# Teensy_Polulu_8848.net
KiCad netlist of a schematic drawn in EAGLE
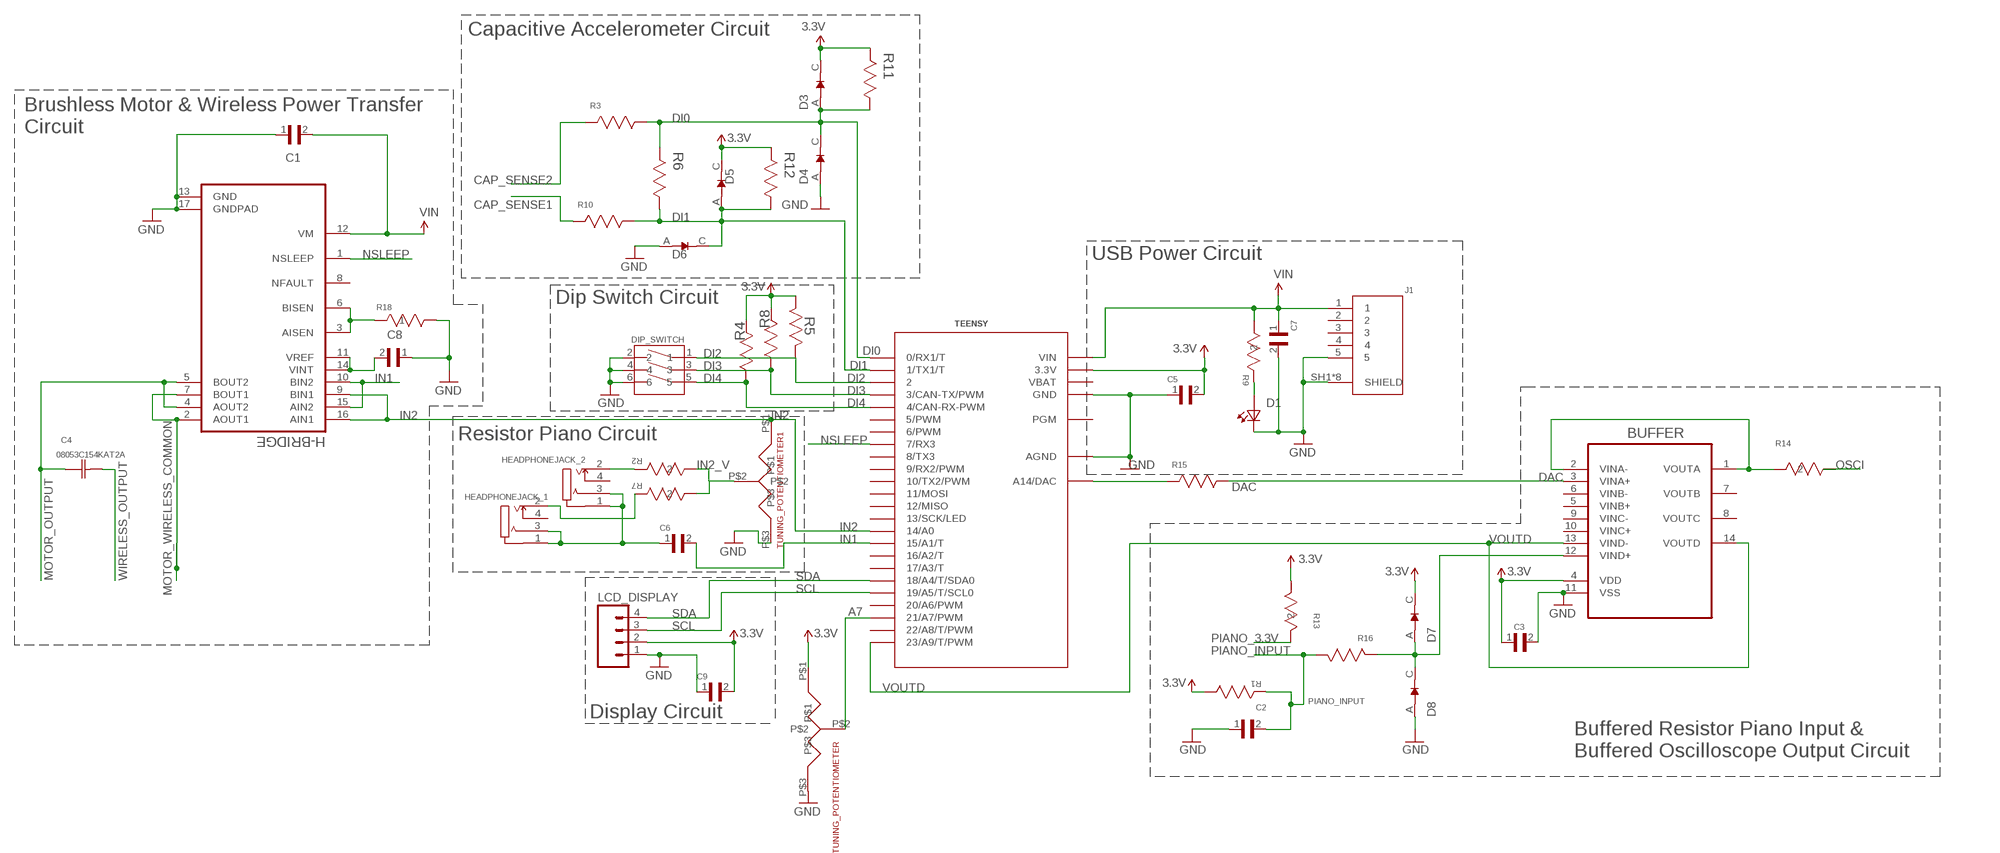
[diagram p0: schematic, sheet 1]

(export (version "E")
  (design (tool "Eeschema 10.0.6"))
  (components
    (comp (ref "BUFFER")
      (value "MCP6024-I/SL")
      (footprint "eagle-import:SOIC127P600X175-14N")
      (fields (field (name "DIGI-KEY_PART_NUMBER") "MCP6024-I/SL-ND") (field (name "MF") "Microchip"))
      (libsource (lib "eagle-import") (part "MCP6024-I/SL"))
    )
    (comp (ref "C1")
      (value "GRM219R60J476ME44D")
      (footprint "eagle-import:CAPC2012X135N")
      (fields (field (name "DIGI-KEY_PART_NUMBER") "490-13249-1-ND") (field (name "MF") "Murata"))
      (libsource (lib "eagle-import") (part "GRM219R60J476ME44D"))
    )
    (comp (ref "C2")
      (value "C2012C0G1V303J060AC")
      (footprint "eagle-import:INDC2012X87N")
      (fields (field (name "MF") "TDK"))
      (libsource (lib "eagle-import") (part "C2012C0G1V303J060AC"))
    )
    (comp (ref "C3")
      (value "GRM219R60J476ME44D")
      (footprint "eagle-import:CAPC2012X135N")
      (fields (field (name "DIGI-KEY_PART_NUMBER") "490-13249-1-ND") (field (name "MF") "Murata"))
      (libsource (lib "eagle-import") (part "GRM219R60J476ME44D"))
    )
    (comp (ref "C4")
      (value "08053C154KAT2A")
      (footprint "eagle-import:CAPC2013X94N")
      (fields (field (name "MF") "AVX"))
      (libsource (lib "eagle-import") (part "08053C154KAT2A"))
    )
    (comp (ref "C5")
      (value "GRM219R60J476ME44D")
      (footprint "eagle-import:CAPC2012X135N")
      (fields (field (name "DIGI-KEY_PART_NUMBER") "490-13249-1-ND") (field (name "MF") "Murata"))
      (libsource (lib "eagle-import") (part "GRM219R60J476ME44D"))
    )
    (comp (ref "C6")
      (value "GRM219R60J476ME44D")
      (footprint "eagle-import:CAPC2012X135N")
      (fields (field (name "DIGI-KEY_PART_NUMBER") "490-13249-1-ND") (field (name "MF") "Murata"))
      (libsource (lib "eagle-import") (part "GRM219R60J476ME44D"))
    )
    (comp (ref "C7")
      (value "GRM219R60J476ME44D")
      (footprint "eagle-import:CAPC2012X135N")
      (fields (field (name "DIGI-KEY_PART_NUMBER") "490-13249-1-ND") (field (name "MF") "Murata"))
      (libsource (lib "eagle-import") (part "GRM219R60J476ME44D"))
    )
    (comp (ref "C8")
      (value "GRM21BR60J225KA01L")
      (footprint "eagle-import:CAPC2012X135N")
      (fields (field (name "DIGI-KEY_PART_NUMBER") "490-1712-1-ND") (field (name "MF") "Murata"))
      (libsource (lib "eagle-import") (part "GRM21BR60J225KA01L"))
    )
    (comp (ref "C9")
      (value "GRM219R60J476ME44D")
      (footprint "eagle-import:CAPC2012X135N")
      (fields (field (name "DIGI-KEY_PART_NUMBER") "490-13249-1-ND") (field (name "MF") "Murata"))
      (libsource (lib "eagle-import") (part "GRM219R60J476ME44D"))
    )
    (comp (ref "D1")
      (value "TLMY1100-GS08")
      (footprint "eagle-import:0603")
      (fields (field (name "MF") "Vishay Semiconductor"))
      (libsource (lib "eagle-import") (part "TLMY1100-GS08"))
    )
    (comp (ref "D3")
      (value "1N4148W-7-F")
      (footprint "eagle-import:SOD3715X135N")
      (fields (field (name "MF") "Diodes Inc."))
      (libsource (lib "eagle-import") (part "1N4148W-7-F"))
    )
    (comp (ref "D4")
      (value "1N4148W-7-F")
      (footprint "eagle-import:SOD3715X135N")
      (fields (field (name "MF") "Diodes Inc."))
      (libsource (lib "eagle-import") (part "1N4148W-7-F"))
    )
    (comp (ref "D5")
      (value "1N4148W-7-F")
      (footprint "eagle-import:SOD3715X135N")
      (fields (field (name "MF") "Diodes Inc."))
      (libsource (lib "eagle-import") (part "1N4148W-7-F"))
    )
    (comp (ref "D6")
      (value "1N4148W-7-F")
      (footprint "eagle-import:SOD3715X135N")
      (fields (field (name "MF") "Diodes Inc."))
      (libsource (lib "eagle-import") (part "1N4148W-7-F"))
    )
    (comp (ref "D7")
      (value "1N4148W-7-F")
      (footprint "eagle-import:SOD3715X135N")
      (fields (field (name "MF") "Diodes Inc."))
      (libsource (lib "eagle-import") (part "1N4148W-7-F"))
    )
    (comp (ref "D8")
      (value "1N4148W-7-F")
      (footprint "eagle-import:SOD3715X135N")
      (fields (field (name "MF") "Diodes Inc."))
      (libsource (lib "eagle-import") (part "1N4148W-7-F"))
    )
    (comp (ref "DIP_SWITCH")
      (value "SDA03H1SBD")
      (footprint "eagle-import:SW_SDA03H1SBD")
      (fields (field (name "MF") "C&K"))
      (libsource (lib "eagle-import") (part "SDA03H1SBD"))
    )
    (comp (ref "H-BRIDGE")
      (value "DRV8848PWP")
      (footprint "eagle-import:SOP65P640X120-17N")
      (fields (field (name "MF") "Texas Instruments"))
      (libsource (lib "eagle-import") (part "DRV8848PWP"))
    )
    (comp (ref "HEADPHONEJACK_1")
      (value "47257-0001")
      (footprint "eagle-import:MOLEX_47257-0001")
      (fields (field (name "MF") "Molex"))
      (libsource (lib "eagle-import") (part "47257-0001"))
    )
    (comp (ref "HEADPHONEJACK_2")
      (value "47257-0001")
      (footprint "eagle-import:MOLEX_47257-0001")
      (fields (field (name "MF") "Molex"))
      (libsource (lib "eagle-import") (part "47257-0001"))
    )
    (comp (ref "J1")
      (value "1050170001")
      (footprint "eagle-import:MOLEX_1050170001")
      (fields (field (name "DIGI-KEY_PART_NUMBER") "WM1399CT-ND") (field (name "MF") "Molex"))
      (libsource (lib "eagle-import") (part "1050170001"))
    )
    (comp (ref "LCD_DISPLAY")
      (value "M04POLAR")
      (footprint "eagle-import:MOLEX-1X4")
      (libsource (lib "eagle-import") (part "M04POLAR"))
    )
    (comp (ref "R1")
      (value "RT0805FRE071ML")
      (footprint "eagle-import:RESC2013X65N")
      (fields (field (name "MF") "Yageo"))
      (libsource (lib "eagle-import") (part "RT0805FRE071ML"))
    )
    (comp (ref "R2")
      (value "RT0805FRE07100RL")
      (footprint "eagle-import:RC0805N")
      (libsource (lib "eagle-import") (part "RT0805FRE07100RL"))
    )
    (comp (ref "R3")
      (value "RT0805FRE0710KL")
      (footprint "eagle-import:RESC2013X65N")
      (fields (field (name "MF") "Yageo") (field (name "SPICEPREFIX") "R"))
      (libsource (lib "eagle-import") (part "RT0805FRE0710KL"))
    )
    (comp (ref "R4")
      (value "RT0805FRE0710KL")
      (footprint "eagle-import:RESC2013X65N")
      (fields (field (name "MF") "Yageo"))
      (libsource (lib "eagle-import") (part "RT0805FRE0710KL"))
    )
    (comp (ref "R5")
      (value "RT0805FRE0710KL")
      (footprint "eagle-import:RESC2013X65N")
      (fields (field (name "MF") "Yageo"))
      (libsource (lib "eagle-import") (part "RT0805FRE0710KL"))
    )
    (comp (ref "R6")
      (value "RT0805FRE071ML")
      (footprint "eagle-import:RESC2013X65N")
      (fields (field (name "MF") "Yageo"))
      (libsource (lib "eagle-import") (part "RT0805FRE071ML"))
    )
    (comp (ref "R7")
      (value "RT0805FRE07100RL")
      (footprint "eagle-import:RC0805N")
      (libsource (lib "eagle-import") (part "RT0805FRE07100RL"))
    )
    (comp (ref "R8")
      (value "RT0805FRE0710KL")
      (footprint "eagle-import:RESC2013X65N")
      (fields (field (name "MF") "Yageo"))
      (libsource (lib "eagle-import") (part "RT0805FRE0710KL"))
    )
    (comp (ref "R9")
      (value "RT0805FRE071KL")
      (footprint "eagle-import:RC0805N")
      (libsource (lib "eagle-import") (part "RT0805FRE071KL"))
    )
    (comp (ref "R10")
      (value "RT0805FRE0710KL")
      (footprint "eagle-import:RESC2013X65N")
      (fields (field (name "MF") "Yageo") (field (name "SPICEPREFIX") "R"))
      (libsource (lib "eagle-import") (part "RT0805FRE0710KL"))
    )
    (comp (ref "R11")
      (value "RT0805FRE071ML")
      (footprint "eagle-import:RESC2013X65N")
      (fields (field (name "MF") "Yageo"))
      (libsource (lib "eagle-import") (part "RT0805FRE071ML"))
    )
    (comp (ref "R12")
      (value "RT0805FRE071ML")
      (footprint "eagle-import:RESC2013X65N")
      (fields (field (name "MF") "Yageo"))
      (libsource (lib "eagle-import") (part "RT0805FRE071ML"))
    )
    (comp (ref "R13")
      (value "RT0805BRD0749R9L")
      (footprint "eagle-import:RC0805N")
      (libsource (lib "eagle-import") (part "RT0805BRD0749R9L"))
    )
    (comp (ref "R14")
      (value "RT0805FRE071KL")
      (footprint "eagle-import:RC0805N")
      (libsource (lib "eagle-import") (part "RT0805FRE071KL"))
    )
    (comp (ref "R15")
      (value "RT0805FRE0710KL")
      (footprint "eagle-import:RESC2013X65N")
      (fields (field (name "MF") "Yageo") (field (name "SPICEPREFIX") "R"))
      (libsource (lib "eagle-import") (part "RT0805FRE0710KL"))
    )
    (comp (ref "R16")
      (value "RT0805FRE0710KL")
      (footprint "eagle-import:RESC2013X65N")
      (fields (field (name "MF") "Yageo") (field (name "SPICEPREFIX") "R"))
      (libsource (lib "eagle-import") (part "RT0805FRE0710KL"))
    )
    (comp (ref "R18")
      (value "CSRN2512FKR250")
      (footprint "eagle-import:STA_CSRN2512")
      (libsource (lib "eagle-import") (part "CSRN2512FKR250"))
    )
    (comp (ref "TEENSY")
      (value "TEENSY_3.1-3.2_OUTER_ROW")
      (footprint "eagle-import:TEENSY_3.0-3.2&LC_OUTER_ROW")
      (libsource (lib "eagle-import") (part "TEENSY_3.1-3.2_OUTER_ROW"))
    )
    (comp (ref "TUNING_POTENTIOMETER")
      (value "POT_PTV09A-4225F-B102-ND")
      (footprint "eagle-import:POT_PTV09A-4225F-B102-ND")
      (libsource (lib "eagle-import") (part "POT_PTV09A-4225F-B102-ND"))
    )
    (comp (ref "TUNING_POTENTIOMETER1")
      (value "POT_PTV09A-4225F-B102-ND")
      (footprint "eagle-import:POT_PTV09A-4225F-B102-ND")
      (libsource (lib "eagle-import") (part "POT_PTV09A-4225F-B102-ND"))
    )
  )
  (nets
    (net (code "1") (name "/A7") (class "Default")
      (node (ref "TEENSY") (pin "21/A7") (pinfunction "21/A7/PWM_21/A7") (pintype "bidirectional"))
      (node (ref "TUNING_POTENTIOMETER") (pin "P$2") (pinfunction "P$2_P$2") (pintype "bidirectional"))
    )
    (net (code "2") (name "/CAP_SENSE1") (class "Default")
      (node (ref "R10") (pin "2") (pinfunction "R2_2") (pintype "passive"))
    )
    (net (code "3") (name "/CAP_SENSE2") (class "Default")
      (node (ref "R3") (pin "2") (pinfunction "R2_2") (pintype "passive"))
    )
    (net (code "4") (name "/DAC") (class "Default")
      (node (ref "BUFFER") (pin "3") (pinfunction "VINA+_3") (pintype "input"))
      (node (ref "R15") (pin "1") (pinfunction "R1_1") (pintype "passive"))
    )
    (net (code "5") (name "/DI0") (class "Default")
      (node (ref "D3") (pin "A") (pinfunction "A_A") (pintype "passive"))
      (node (ref "D4") (pin "C") (pinfunction "K_C") (pintype "passive"))
      (node (ref "R11") (pin "1") (pinfunction "R1_1") (pintype "passive"))
      (node (ref "R3") (pin "1") (pinfunction "R1_1") (pintype "passive"))
      (node (ref "R6") (pin "2") (pinfunction "R2_2") (pintype "passive"))
      (node (ref "TEENSY") (pin "0") (pinfunction "0/RX1/T_0") (pintype "bidirectional"))
    )
    (net (code "6") (name "/DI1") (class "Default")
      (node (ref "D5") (pin "A") (pinfunction "A_A") (pintype "passive"))
      (node (ref "D6") (pin "C") (pinfunction "K_C") (pintype "passive"))
      (node (ref "R10") (pin "1") (pinfunction "R1_1") (pintype "passive"))
      (node (ref "R12") (pin "1") (pinfunction "R1_1") (pintype "passive"))
      (node (ref "R6") (pin "1") (pinfunction "R1_1") (pintype "passive"))
      (node (ref "TEENSY") (pin "1") (pinfunction "1/TX1/T_1") (pintype "bidirectional"))
    )
    (net (code "7") (name "/DI2") (class "Default")
      (node (ref "DIP_SWITCH") (pin "1") (pinfunction "1_1") (pintype "passive"))
      (node (ref "R5") (pin "2") (pinfunction "R2_2") (pintype "passive"))
      (node (ref "TEENSY") (pin "2") (pinfunction "2_2") (pintype "bidirectional"))
    )
    (net (code "8") (name "/DI3") (class "Default")
      (node (ref "DIP_SWITCH") (pin "3") (pinfunction "3_3") (pintype "passive"))
      (node (ref "R8") (pin "2") (pinfunction "R2_2") (pintype "passive"))
      (node (ref "TEENSY") (pin "3") (pinfunction "3/CAN-TX/PWM_3") (pintype "bidirectional"))
    )
    (net (code "9") (name "/DI4") (class "Default")
      (node (ref "DIP_SWITCH") (pin "5") (pinfunction "5_5") (pintype "passive"))
      (node (ref "R4") (pin "2") (pinfunction "R2_2") (pintype "passive"))
      (node (ref "TEENSY") (pin "4") (pinfunction "4/CAN-RX-PWM_4") (pintype "bidirectional"))
    )
    (net (code "10") (name "/IN1") (class "Default")
      (node (ref "C6") (pin "2") (pinfunction "2_2") (pintype "passive"))
      (node (ref "H-BRIDGE") (pin "10") (pinfunction "BIN2_10") (pintype "input"))
      (node (ref "H-BRIDGE") (pin "15") (pinfunction "AIN2_15") (pintype "input"))
      (node (ref "TEENSY") (pin "15/A1") (pinfunction "15/A1/T_15/A1") (pintype "bidirectional"))
    )
    (net (code "11") (name "/IN2") (class "Default")
      (node (ref "H-BRIDGE") (pin "16") (pinfunction "AIN1_16") (pintype "input"))
      (node (ref "H-BRIDGE") (pin "9") (pinfunction "BIN1_9") (pintype "input"))
      (node (ref "TEENSY") (pin "14/A0") (pinfunction "14/A0_14/A0") (pintype "bidirectional"))
      (node (ref "TUNING_POTENTIOMETER1") (pin "P$1") (pinfunction "P$1_P$1") (pintype "bidirectional"))
    )
    (net (code "12") (name "/IN2_V") (class "Default")
      (node (ref "R2") (pin "2") (pinfunction "2_2") (pintype "passive"))
      (node (ref "R7") (pin "2") (pinfunction "2_2") (pintype "passive"))
      (node (ref "TUNING_POTENTIOMETER1") (pin "P$2") (pinfunction "P$2_P$2") (pintype "bidirectional"))
    )
    (net (code "13") (name "/MOTOR_OUTPUT") (class "Default")
      (node (ref "C4") (pin "1") (pinfunction "C1_1") (pintype "passive"))
      (node (ref "H-BRIDGE") (pin "4") (pinfunction "AOUT2_4") (pintype "output"))
      (node (ref "H-BRIDGE") (pin "5") (pinfunction "BOUT2_5") (pintype "output"))
    )
    (net (code "14") (name "/MOTOR_WIRELESS_COMMON") (class "Default")
      (node (ref "H-BRIDGE") (pin "2") (pinfunction "AOUT1_2") (pintype "output"))
      (node (ref "H-BRIDGE") (pin "7") (pinfunction "BOUT1_7") (pintype "output"))
    )
    (net (code "15") (name "/NSLEEP") (class "Default")
      (node (ref "H-BRIDGE") (pin "1") (pinfunction "NSLEEP_1") (pintype "bidirectional"))
      (node (ref "TEENSY") (pin "7") (pinfunction "7/RX3_7") (pintype "bidirectional"))
    )
    (net (code "16") (name "/OSCI") (class "Default")
      (node (ref "R14") (pin "1") (pinfunction "1_1") (pintype "passive"))
    )
    (net (code "17") (name "/PIANO_3.3V") (class "Default")
      (node (ref "R13") (pin "2") (pinfunction "2_2") (pintype "passive"))
    )
    (net (code "18") (name "/PIANO_INPUT") (class "Default")
      (node (ref "C2") (pin "2") (pinfunction "2_2") (pintype "passive"))
      (node (ref "R1") (pin "2") (pinfunction "R2_2") (pintype "passive"))
      (node (ref "R16") (pin "1") (pinfunction "R1_1") (pintype "passive"))
    )
    (net (code "19") (name "/SCL") (class "Default")
      (node (ref "LCD_DISPLAY") (pin "3") (pinfunction "3_3") (pintype "passive"))
      (node (ref "TEENSY") (pin "19/A5") (pinfunction "19/A5/T/SCL0_19/A5") (pintype "bidirectional"))
    )
    (net (code "20") (name "/SDA") (class "Default")
      (node (ref "LCD_DISPLAY") (pin "4") (pinfunction "4_4") (pintype "passive"))
      (node (ref "TEENSY") (pin "18/A4") (pinfunction "18/A4/T/SDA0_18/A4") (pintype "bidirectional"))
    )
    (net (code "21") (name "/VBAT") (class "Default")
      (node (ref "TEENSY") (pin "VBAT") (pinfunction "VBAT_VBAT") (pintype "power_in"))
    )
    (net (code "22") (name "/VOUTD") (class "Default")
      (node (ref "BUFFER") (pin "13") (pinfunction "VIND-_13") (pintype "input"))
      (node (ref "BUFFER") (pin "14") (pinfunction "VOUTD_14") (pintype "output"))
      (node (ref "TEENSY") (pin "23/A9") (pinfunction "23/A9/T/PWM_23/A9") (pintype "bidirectional"))
    )
    (net (code "23") (name "/WIRELESS_OUTPUT") (class "Default")
      (node (ref "C4") (pin "2") (pinfunction "C2_2") (pintype "passive"))
    )
    (net (code "24") (name "3.3V") (class "Default")
      (node (ref "BUFFER") (pin "4") (pinfunction "VDD_4") (pintype "power_in"))
      (node (ref "C3") (pin "1") (pinfunction "1_1") (pintype "passive"))
      (node (ref "C5") (pin "2") (pinfunction "2_2") (pintype "passive"))
      (node (ref "C9") (pin "2") (pinfunction "2_2") (pintype "passive"))
      (node (ref "D3") (pin "C") (pinfunction "K_C") (pintype "passive"))
      (node (ref "D5") (pin "C") (pinfunction "K_C") (pintype "passive"))
      (node (ref "D7") (pin "C") (pinfunction "K_C") (pintype "passive"))
      (node (ref "LCD_DISPLAY") (pin "2") (pinfunction "2_2") (pintype "passive"))
      (node (ref "R1") (pin "1") (pinfunction "R1_1") (pintype "passive"))
      (node (ref "R11") (pin "2") (pinfunction "R2_2") (pintype "passive"))
      (node (ref "R12") (pin "2") (pinfunction "R2_2") (pintype "passive"))
      (node (ref "R13") (pin "1") (pinfunction "1_1") (pintype "passive"))
      (node (ref "R4") (pin "1") (pinfunction "R1_1") (pintype "passive"))
      (node (ref "R5") (pin "1") (pinfunction "R1_1") (pintype "passive"))
      (node (ref "R8") (pin "1") (pinfunction "R1_1") (pintype "passive"))
      (node (ref "TEENSY") (pin "3.3V") (pinfunction "3.3V_3.3V") (pintype "power_in"))
      (node (ref "TEENSY") (pin "3.3V1") (pinfunction "3.3V_3.3V1") (pintype "power_in"))
      (node (ref "TUNING_POTENTIOMETER") (pin "P$1") (pinfunction "P$1_P$1") (pintype "bidirectional"))
    )
    (net (code "25") (name "GND") (class "Default")
      (node (ref "BUFFER") (pin "11") (pinfunction "VSS_11") (pintype "passive"))
      (node (ref "C1") (pin "1") (pinfunction "1_1") (pintype "passive"))
      (node (ref "C2") (pin "1") (pinfunction "1_1") (pintype "passive"))
      (node (ref "C3") (pin "2") (pinfunction "2_2") (pintype "passive"))
      (node (ref "C5") (pin "1") (pinfunction "1_1") (pintype "passive"))
      (node (ref "C7") (pin "2") (pinfunction "2_2") (pintype "passive"))
      (node (ref "C8") (pin "1") (pinfunction "1_1") (pintype "passive"))
      (node (ref "C9") (pin "1") (pinfunction "1_1") (pintype "passive"))
      (node (ref "D1") (pin "1") (pinfunction "K2_1") (pintype "passive"))
      (node (ref "D4") (pin "A") (pinfunction "A_A") (pintype "passive"))
      (node (ref "D6") (pin "A") (pinfunction "A_A") (pintype "passive"))
      (node (ref "D8") (pin "A") (pinfunction "A_A") (pintype "passive"))
      (node (ref "DIP_SWITCH") (pin "2") (pinfunction "2_2") (pintype "passive"))
      (node (ref "DIP_SWITCH") (pin "4") (pinfunction "4_4") (pintype "passive"))
      (node (ref "DIP_SWITCH") (pin "6") (pinfunction "6_6") (pintype "passive"))
      (node (ref "H-BRIDGE") (pin "13") (pinfunction "GND_13") (pintype "power_in"))
      (node (ref "H-BRIDGE") (pin "17") (pinfunction "GNDPAD_17") (pintype "power_in"))
      (node (ref "J1") (pin "5") (pinfunction "5_5") (pintype "passive"))
      (node (ref "J1") (pin "SH1") (pinfunction "SHIELD_SH1") (pintype "passive"))
      (node (ref "J1") (pin "SH2") (pinfunction "SHIELD_SH2") (pintype "passive"))
      (node (ref "J1") (pin "SH3") (pinfunction "SHIELD_SH3") (pintype "passive"))
      (node (ref "J1") (pin "SH4") (pinfunction "SHIELD_SH4") (pintype "passive"))
      (node (ref "J1") (pin "SH5") (pinfunction "SHIELD_SH5") (pintype "passive"))
      (node (ref "J1") (pin "SH6") (pinfunction "SHIELD_SH6") (pintype "passive"))
      (node (ref "J1") (pin "SH7") (pinfunction "SHIELD_SH7") (pintype "passive"))
      (node (ref "J1") (pin "SH8") (pinfunction "SHIELD_SH8") (pintype "passive"))
      (node (ref "LCD_DISPLAY") (pin "1") (pinfunction "1_1") (pintype "passive"))
      (node (ref "R18") (pin "2") (pinfunction "2_2") (pintype "passive"))
      (node (ref "TEENSY") (pin "AGND") (pinfunction "AGND_AGND") (pintype "power_in"))
      (node (ref "TEENSY") (pin "GND") (pinfunction "GND_GND") (pintype "power_in"))
      (node (ref "TEENSY") (pin "GND1") (pinfunction "GND_GND1") (pintype "power_in"))
      (node (ref "TUNING_POTENTIOMETER") (pin "P$3") (pinfunction "P$3_P$3") (pintype "bidirectional"))
      (node (ref "TUNING_POTENTIOMETER1") (pin "P$3") (pinfunction "P$3_P$3") (pintype "bidirectional"))
    )
    (net (code "26") (name "Net-(BUFFER-VINA-)") (class "Default")
      (node (ref "BUFFER") (pin "1") (pinfunction "VOUTA_1") (pintype "output"))
      (node (ref "BUFFER") (pin "2") (pinfunction "VINA-_2") (pintype "input"))
      (node (ref "R14") (pin "2") (pinfunction "2_2") (pintype "passive"))
    )
    (net (code "27") (name "Net-(BUFFER-VIND+)") (class "Default")
      (node (ref "BUFFER") (pin "12") (pinfunction "VIND+_12") (pintype "input"))
      (node (ref "D7") (pin "A") (pinfunction "A_A") (pintype "passive"))
      (node (ref "D8") (pin "C") (pinfunction "K_C") (pintype "passive"))
      (node (ref "R16") (pin "2") (pinfunction "R2_2") (pintype "passive"))
    )
    (net (code "28") (name "Net-(C6-Pad1)") (class "Default")
      (node (ref "C6") (pin "1") (pinfunction "1_1") (pintype "passive"))
      (node (ref "HEADPHONEJACK_1") (pin "1") (pinfunction "1_1") (pintype "passive"))
      (node (ref "HEADPHONEJACK_1") (pin "3") (pinfunction "3_3") (pintype "passive"))
      (node (ref "HEADPHONEJACK_2") (pin "1") (pinfunction "1_1") (pintype "passive"))
      (node (ref "HEADPHONEJACK_2") (pin "3") (pinfunction "3_3") (pintype "passive"))
    )
    (net (code "29") (name "Net-(D1-A2)") (class "Default")
      (node (ref "D1") (pin "2") (pinfunction "A2_2") (pintype "passive"))
      (node (ref "R9") (pin "1") (pinfunction "1_1") (pintype "passive"))
    )
    (net (code "30") (name "Net-(H-BRIDGE-AISEN)") (class "Default")
      (node (ref "H-BRIDGE") (pin "3") (pinfunction "AISEN_3") (pintype "bidirectional"))
      (node (ref "H-BRIDGE") (pin "6") (pinfunction "BISEN_6") (pintype "bidirectional"))
      (node (ref "R18") (pin "1") (pinfunction "1_1") (pintype "passive"))
    )
    (net (code "31") (name "Net-(H-BRIDGE-VINT)") (class "Default")
      (node (ref "C8") (pin "2") (pinfunction "2_2") (pintype "passive"))
      (node (ref "H-BRIDGE") (pin "11") (pinfunction "VREF_11") (pintype "input"))
      (node (ref "H-BRIDGE") (pin "14") (pinfunction "VINT_14") (pintype "input"))
    )
    (net (code "32") (name "Net-(HEADPHONEJACK_1-Pad2)") (class "Default")
      (node (ref "HEADPHONEJACK_1") (pin "2") (pinfunction "2_2") (pintype "passive"))
      (node (ref "R7") (pin "1") (pinfunction "1_1") (pintype "passive"))
    )
    (net (code "33") (name "Net-(HEADPHONEJACK_2-Pad2)") (class "Default")
      (node (ref "HEADPHONEJACK_2") (pin "2") (pinfunction "2_2") (pintype "passive"))
      (node (ref "R2") (pin "1") (pinfunction "1_1") (pintype "passive"))
    )
    (net (code "34") (name "Net-(R15-R2)") (class "Default")
      (node (ref "R15") (pin "2") (pinfunction "R2_2") (pintype "passive"))
      (node (ref "TEENSY") (pin "RESET/DAC") (pinfunction "A14/DAC_RESET/DAC") (pintype "bidirectional"))
    )
    (net (code "35") (name "VIN") (class "Default")
      (node (ref "C1") (pin "2") (pinfunction "2_2") (pintype "passive"))
      (node (ref "C7") (pin "1") (pinfunction "1_1") (pintype "passive"))
      (node (ref "H-BRIDGE") (pin "12") (pinfunction "VM_12") (pintype "bidirectional"))
      (node (ref "J1") (pin "1") (pinfunction "1_1") (pintype "passive"))
      (node (ref "R9") (pin "2") (pinfunction "2_2") (pintype "passive"))
      (node (ref "TEENSY") (pin "VIN") (pinfunction "VIN_VIN") (pintype "power_in"))
    )
    (net (code "36") (name "unconnected-(BUFFER-VINB+-Pad5)") (class "Default")
      (node (ref "BUFFER") (pin "5") (pinfunction "VINB+_5") (pintype "input"))
    )
    (net (code "37") (name "unconnected-(BUFFER-VINB--Pad6)") (class "Default")
      (node (ref "BUFFER") (pin "6") (pinfunction "VINB-_6") (pintype "input"))
    )
    (net (code "38") (name "unconnected-(BUFFER-VINC+-Pad10)") (class "Default")
      (node (ref "BUFFER") (pin "10") (pinfunction "VINC+_10") (pintype "input"))
    )
    (net (code "39") (name "unconnected-(BUFFER-VINC--Pad9)") (class "Default")
      (node (ref "BUFFER") (pin "9") (pinfunction "VINC-_9") (pintype "input"))
    )
    (net (code "40") (name "unconnected-(BUFFER-VOUTB-Pad7)") (class "Default")
      (node (ref "BUFFER") (pin "7") (pinfunction "VOUTB_7") (pintype "output"))
    )
    (net (code "41") (name "unconnected-(BUFFER-VOUTC-Pad8)") (class "Default")
      (node (ref "BUFFER") (pin "8") (pinfunction "VOUTC_8") (pintype "output"))
    )
    (net (code "42") (name "unconnected-(H-BRIDGE-NFAULT-Pad8)") (class "Default")
      (node (ref "H-BRIDGE") (pin "8") (pinfunction "NFAULT_8") (pintype "bidirectional"))
    )
    (net (code "43") (name "unconnected-(HEADPHONEJACK_1-Pad4)") (class "Default")
      (node (ref "HEADPHONEJACK_1") (pin "4") (pinfunction "4_4") (pintype "passive"))
    )
    (net (code "44") (name "unconnected-(HEADPHONEJACK_2-Pad4)") (class "Default")
      (node (ref "HEADPHONEJACK_2") (pin "4") (pinfunction "4_4") (pintype "passive"))
    )
    (net (code "45") (name "unconnected-(J1-Pad2)") (class "Default")
      (node (ref "J1") (pin "2") (pinfunction "2_2") (pintype "passive"))
    )
    (net (code "46") (name "unconnected-(J1-Pad3)") (class "Default")
      (node (ref "J1") (pin "3") (pinfunction "3_3") (pintype "passive"))
    )
    (net (code "47") (name "unconnected-(J1-Pad4)") (class "Default")
      (node (ref "J1") (pin "4") (pinfunction "4_4") (pintype "passive"))
    )
    (net (code "48") (name "unconnected-(TEENSY-5{slash}PWM-Pad5)") (class "Default")
      (node (ref "TEENSY") (pin "5") (pinfunction "5/PWM_5") (pintype "bidirectional"))
    )
    (net (code "49") (name "unconnected-(TEENSY-6{slash}PWM-Pad6)") (class "Default")
      (node (ref "TEENSY") (pin "6") (pinfunction "6/PWM_6") (pintype "bidirectional"))
    )
    (net (code "50") (name "unconnected-(TEENSY-8{slash}TX3-Pad8)") (class "Default")
      (node (ref "TEENSY") (pin "8") (pinfunction "8/TX3_8") (pintype "bidirectional"))
    )
    (net (code "51") (name "unconnected-(TEENSY-9{slash}RX2{slash}PWM-Pad9)") (class "Default")
      (node (ref "TEENSY") (pin "9") (pinfunction "9/RX2/PWM_9") (pintype "bidirectional"))
    )
    (net (code "52") (name "unconnected-(TEENSY-10{slash}TX2{slash}PWM-Pad10)") (class "Default")
      (node (ref "TEENSY") (pin "10") (pinfunction "10/TX2/PWM_10") (pintype "bidirectional"))
    )
    (net (code "53") (name "unconnected-(TEENSY-11{slash}MOSI-Pad11)") (class "Default")
      (node (ref "TEENSY") (pin "11") (pinfunction "11/MOSI_11") (pintype "bidirectional"))
    )
    (net (code "54") (name "unconnected-(TEENSY-12{slash}MISO-Pad12)") (class "Default")
      (node (ref "TEENSY") (pin "12") (pinfunction "12/MISO_12") (pintype "bidirectional"))
    )
    (net (code "55") (name "unconnected-(TEENSY-13{slash}SCK{slash}LED-Pad13)") (class "Default")
      (node (ref "TEENSY") (pin "13") (pinfunction "13/SCK/LED_13") (pintype "bidirectional"))
    )
    (net (code "56") (name "unconnected-(TEENSY-16{slash}A2{slash}T-Pad16{slash}A2)") (class "Default")
      (node (ref "TEENSY") (pin "16/A2") (pinfunction "16/A2/T_16/A2") (pintype "bidirectional"))
    )
    (net (code "57") (name "unconnected-(TEENSY-17{slash}A3{slash}T-Pad17{slash}A3)") (class "Default")
      (node (ref "TEENSY") (pin "17/A3") (pinfunction "17/A3/T_17/A3") (pintype "bidirectional"))
    )
    (net (code "58") (name "unconnected-(TEENSY-20{slash}A6{slash}PWM-Pad20{slash}A6)") (class "Default")
      (node (ref "TEENSY") (pin "20/A6") (pinfunction "20/A6/PWM_20/A6") (pintype "bidirectional"))
    )
    (net (code "59") (name "unconnected-(TEENSY-22{slash}A8{slash}T{slash}PWM-Pad22{slash}A8)") (class "Default")
      (node (ref "TEENSY") (pin "22/A8") (pinfunction "22/A8/T/PWM_22/A8") (pintype "bidirectional"))
    )
    (net (code "60") (name "unconnected-(TEENSY-PadPGM)") (class "Default")
      (node (ref "TEENSY") (pin "PGM") (pinfunction "PGM_PGM") (pintype "bidirectional"))
    )
  )
)
